# PowerInjeect.net
KiCad netlist of a schematic drawn in EAGLE
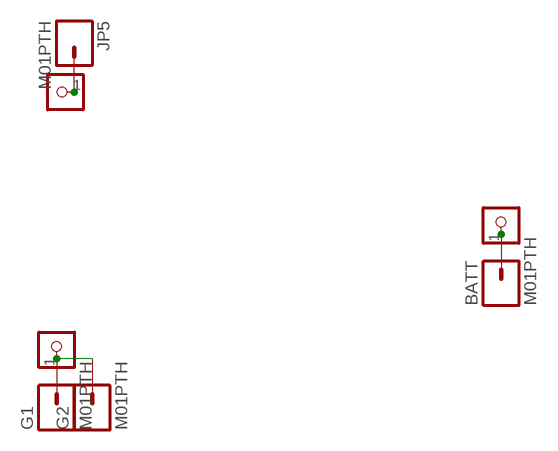
[diagram p0: schematic, sheet 1]

(export (version "E")
  (design (tool "Eeschema 10.0.6"))
  (components
    (comp (ref "BATT")
      (value "M01PTH")
      (footprint "eagle-import:1X01")
      (libsource (lib "eagle-import") (part "M01PTH"))
    )
    (comp (ref "G1")
      (value "M01PTH")
      (footprint "eagle-import:1X01")
      (libsource (lib "eagle-import") (part "M01PTH"))
    )
    (comp (ref "G2")
      (value "M01PTH")
      (footprint "eagle-import:1X01")
      (libsource (lib "eagle-import") (part "M01PTH"))
    )
    (comp (ref "J2")
      (value "CON_HEADER_1X01-PTH_10_17")
      (footprint "eagle-import:M1X2_10_17")
      (libsource (lib "eagle-import") (part "CON_HEADER_1X01-PTH_10_17"))
    )
    (comp (ref "J3")
      (value "CON_HEADER_1X01-PTH_10_17")
      (footprint "eagle-import:M1X2_10_17")
      (libsource (lib "eagle-import") (part "CON_HEADER_1X01-PTH_10_17"))
    )
    (comp (ref "J6")
      (value "CON_HEADER_1X01-PTH_10_17")
      (footprint "eagle-import:M1X2_10_17")
      (libsource (lib "eagle-import") (part "CON_HEADER_1X01-PTH_10_17"))
    )
    (comp (ref "JP5")
      (value "M01PTH")
      (footprint "eagle-import:1X01")
      (libsource (lib "eagle-import") (part "M01PTH"))
    )
  )
  (nets
    (net (code "1") (name "Net-(BATT-Pad1)") (class "Default")
      (node (ref "BATT") (pin "1") (pinfunction "1_1") (pintype "passive"))
      (node (ref "J6") (pin "1") (pinfunction "1_1") (pintype "passive"))
    )
    (net (code "2") (name "Net-(G1-Pad1)") (class "Default")
      (node (ref "G1") (pin "1") (pinfunction "1_1") (pintype "passive"))
      (node (ref "G2") (pin "1") (pinfunction "1_1") (pintype "passive"))
      (node (ref "J3") (pin "1") (pinfunction "1_1") (pintype "passive"))
    )
    (net (code "3") (name "Net-(J2-Pad1)") (class "Default")
      (node (ref "J2") (pin "1") (pinfunction "1_1") (pintype "passive"))
      (node (ref "JP5") (pin "1") (pinfunction "1_1") (pintype "passive"))
    )
  )
)
